# PowerMiscelenaus.net
KiCad netlist of a schematic drawn in Altium Designer
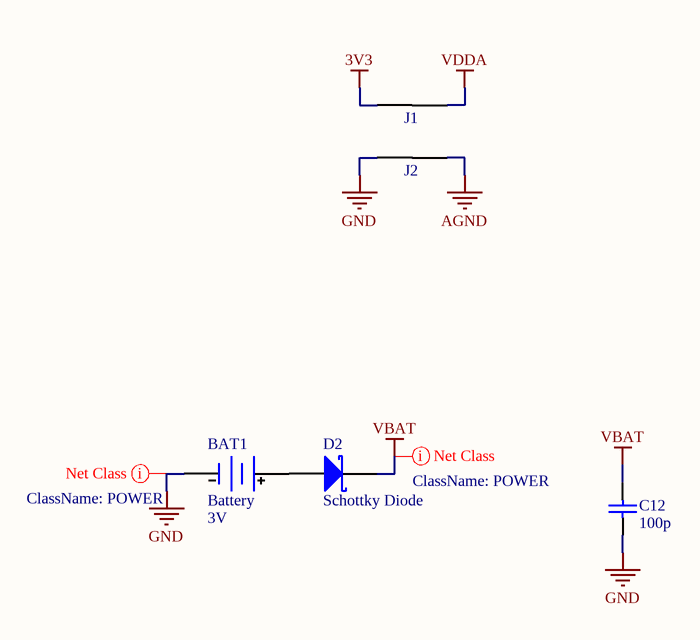
[diagram p0: PowerMiscelenaus.SchDoc]

(export (version "E")
  (design (tool "Eeschema 10.0.6"))
  (components
    (comp (ref "BAT1")
      (value "Battery")
      (footprint "KEYSTONE 1056")
      (fields (field (name "ALTIUM_VALUE") "3V"))
      (libsource (lib "agh_racing_2018") (part "BATT"))
    )
    (comp (ref "C12")
      (value "100p")
      (footprint "agh_racing_2018:CAP_0603_IPC_MD")
      (description "Capacitor")
      (fields (field (name "Comment") "Cap"))
      (libsource (lib "agh_racing_2018") (part "Cap"))
    )
    (comp (ref "D2")
      (value "Schottky Diode")
      (footprint "MiniMELF_IPC_MD")
      (fields
        (field (name "MANUFACTURER") "VISHAY")
        (field (name "MANUFACTURER PART NUMBER") "LL42-GS08 (for MiniMELF)")
      )
      (libsource (lib "agh_racing_2018") (part "Schottky Diode"))
    )
    (comp (ref "J1")
      (value "NetTie")
      (footprint "agh_racing_2018:NETTIE")
      (libsource (lib "agh_racing_2018") (part "NetTie"))
    )
    (comp (ref "J2")
      (value "NetTie")
      (footprint "agh_racing_2018:NETTIE")
      (libsource (lib "agh_racing_2018") (part "NetTie"))
    )
  )
  (nets
    (net (code "1") (name "3V3") (class "Default")
      (node (ref "J1") (pin "1") (pinfunction "1_1") (pintype "passive"))
    )
    (net (code "2") (name "AGND") (class "Default")
      (node (ref "J2") (pin "2") (pinfunction "2_2") (pintype "passive"))
    )
    (net (code "3") (name "GND") (class "Default")
      (node (ref "BAT1") (pin "2") (pinfunction "-_2") (pintype "passive"))
      (node (ref "C12") (pin "1") (pinfunction "1_1") (pintype "passive"))
      (node (ref "J2") (pin "1") (pinfunction "1_1") (pintype "passive"))
    )
    (net (code "4") (name "Net-(BAT1-+)") (class "Default")
      (node (ref "BAT1") (pin "1") (pinfunction "+_1") (pintype "passive"))
      (node (ref "D2") (pin "1") (pinfunction "A_1") (pintype "passive"))
    )
    (net (code "5") (name "VBAT") (class "Default")
      (node (ref "C12") (pin "2") (pinfunction "2_2") (pintype "passive"))
      (node (ref "D2") (pin "2") (pinfunction "K_2") (pintype "passive"))
    )
    (net (code "6") (name "VDDA") (class "Default")
      (node (ref "J1") (pin "2") (pinfunction "2_2") (pintype "passive"))
    )
  )
)
